# circuit_protection.net
KiCad netlist of a schematic drawn in EAGLE
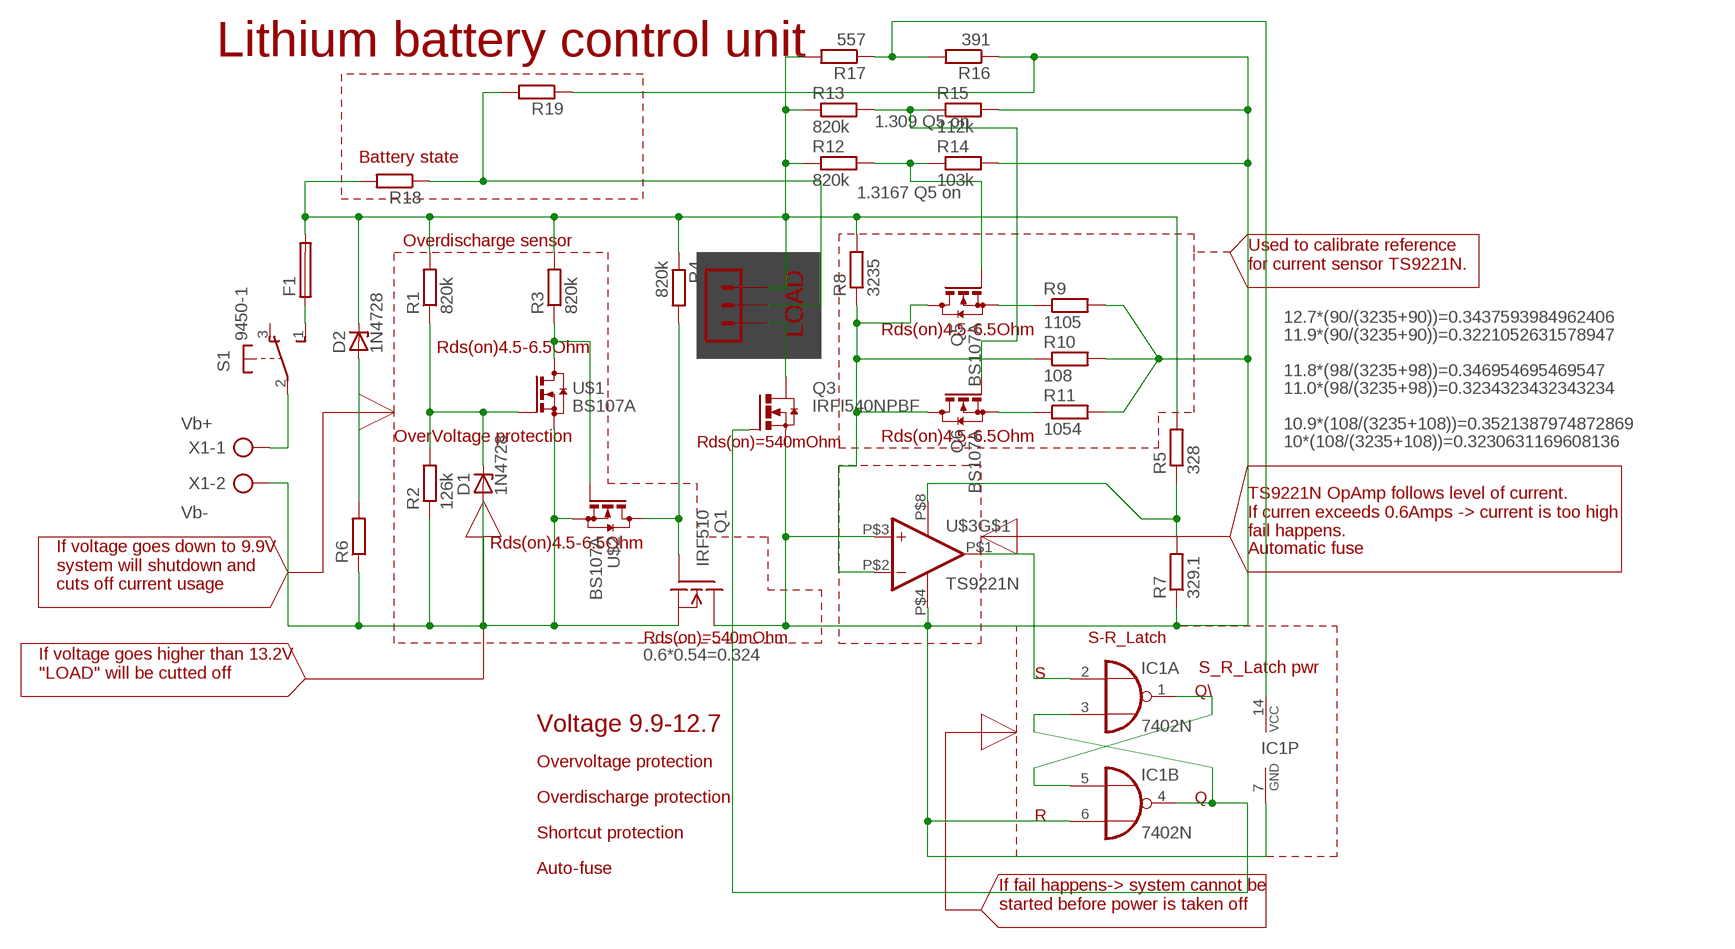
[diagram p0: schematic, sheet 1]

(export (version "E")
  (design (tool "Eeschema 10.0.6"))
  (components
    (comp (ref "D1")
      (value "1N4728")
      (footprint "eagle-import:DO41Z10")
      (libsource (lib "eagle-import") (part "1N4728"))
    )
    (comp (ref "D2")
      (value "1N4728")
      (footprint "eagle-import:DO41Z10")
      (libsource (lib "eagle-import") (part "1N4728"))
    )
    (comp (ref "F1")
      (value "GSH15")
      (footprint "eagle-import:GSH15")
      (fields (field (name "MPN") "64900001039"))
      (libsource (lib "eagle-import") (part "GSH15"))
    )
    (comp (ref "IC1")
      (value "7402N")
      (footprint "eagle-import:DIL14")
      (libsource (lib "eagle-import") (part "7402N"))
    )
    (comp (ref "Q1")
      (value "IRF510")
      (footprint "eagle-import:TO220")
      (libsource (lib "eagle-import") (part "IRF510"))
    )
    (comp (ref "Q3")
      (value "IRFI540NPBF")
      (footprint "eagle-import:TO220BH")
      (libsource (lib "eagle-import") (part "IRFI540NPBF"))
    )
    (comp (ref "Q5")
      (value "BS107A")
      (footprint "eagle-import:BC877")
      (libsource (lib "eagle-import") (part "BS107A"))
    )
    (comp (ref "Q6")
      (value "BS107A")
      (footprint "eagle-import:BC877")
      (libsource (lib "eagle-import") (part "BS107A"))
    )
    (comp (ref "R1")
      (value "820k")
      (footprint "eagle-import:0204_7")
      (libsource (lib "eagle-import") (part "R-EU_0204/7"))
    )
    (comp (ref "R2")
      (value "126k")
      (footprint "eagle-import:0204_7")
      (libsource (lib "eagle-import") (part "R-EU_0204/7"))
    )
    (comp (ref "R3")
      (value "820k")
      (footprint "eagle-import:0204_7")
      (libsource (lib "eagle-import") (part "resistor_R-EU_0204/7"))
    )
    (comp (ref "R4")
      (value "820k")
      (footprint "eagle-import:0204_7")
      (libsource (lib "eagle-import") (part "resistor_R-EU_0204/7"))
    )
    (comp (ref "R5")
      (value "328")
      (footprint "eagle-import:0204_7")
      (libsource (lib "eagle-import") (part "R-EU_0204/7"))
    )
    (comp (ref "R6")
      (value "R-EU_0204/7")
      (footprint "eagle-import:0204_7")
      (libsource (lib "eagle-import") (part "resistor_R-EU_0204/7"))
    )
    (comp (ref "R7")
      (value "329.1")
      (footprint "eagle-import:0204_7")
      (libsource (lib "eagle-import") (part "R-EU_0204/7"))
    )
    (comp (ref "R8")
      (value "3235")
      (footprint "eagle-import:0204_7")
      (libsource (lib "eagle-import") (part "R-EU_0204/7"))
    )
    (comp (ref "R9")
      (value "1105")
      (footprint "eagle-import:0204_7")
      (libsource (lib "eagle-import") (part "R-EU_0204/7"))
    )
    (comp (ref "R10")
      (value "108")
      (footprint "eagle-import:0204_7")
      (libsource (lib "eagle-import") (part "R-EU_0204/7"))
    )
    (comp (ref "R11")
      (value "1054")
      (footprint "eagle-import:0204_7")
      (libsource (lib "eagle-import") (part "R-EU_0204/7"))
    )
    (comp (ref "R12")
      (value "820k")
      (footprint "eagle-import:0204_7")
      (libsource (lib "eagle-import") (part "R-EU_0204/7"))
    )
    (comp (ref "R13")
      (value "820k")
      (footprint "eagle-import:0204_7")
      (libsource (lib "eagle-import") (part "R-EU_0204/7"))
    )
    (comp (ref "R14")
      (value "103k")
      (footprint "eagle-import:0204_7")
      (libsource (lib "eagle-import") (part "R-EU_0204/7"))
    )
    (comp (ref "R15")
      (value "112k")
      (footprint "eagle-import:0204_7")
      (libsource (lib "eagle-import") (part "R-EU_0204/7"))
    )
    (comp (ref "R16")
      (value "391")
      (footprint "eagle-import:0204_7")
      (libsource (lib "eagle-import") (part "resistor_R-EU_0204/7"))
    )
    (comp (ref "R17")
      (value "557")
      (footprint "eagle-import:0204_7")
      (libsource (lib "eagle-import") (part "resistor_R-EU_0204/7"))
    )
    (comp (ref "R18")
      (value "R-EU_0204/7")
      (footprint "eagle-import:0204_7")
      (libsource (lib "eagle-import") (part "resistor_R-EU_0204/7"))
    )
    (comp (ref "R19")
      (value "R-EU_0204/7")
      (footprint "eagle-import:0204_7")
      (libsource (lib "eagle-import") (part "resistor_R-EU_0204/7"))
    )
    (comp (ref "S1")
      (value "9450-1")
      (footprint "eagle-import:9450-1")
      (libsource (lib "eagle-import") (part "9450-1"))
    )
    (comp (ref "SV1")
      (value "MA03-1")
      (footprint "eagle-import:MA03-1")
      (libsource (lib "eagle-import") (part "MA03-1"))
    )
    (comp (ref "U$1")
      (value "BS107A")
      (footprint "eagle-import:BC877")
      (libsource (lib "eagle-import") (part "BS107A"))
    )
    (comp (ref "U$2")
      (value "BS107A")
      (footprint "eagle-import:BC877")
      (libsource (lib "eagle-import") (part "BS107A"))
    )
    (comp (ref "U$3")
      (value "TS9221N")
      (footprint "eagle-import:DIP08")
      (libsource (lib "eagle-import") (part "TS9221N"))
    )
    (comp (ref "X1")
      (value "AK300/2")
      (footprint "eagle-import:AK300_2")
      (libsource (lib "eagle-import") (part "AK300/2"))
    )
  )
  (nets
    (net (code "1") (name "Net-(D2-PadA)") (class "Default")
      (node (ref "D2") (pin "A") (pinfunction "A_A") (pintype "passive"))
      (node (ref "R6") (pin "2") (pinfunction "2_2") (pintype "passive"))
    )
    (net (code "2") (name "Net-(D2-PadC)") (class "Default")
      (node (ref "D2") (pin "C") (pinfunction "C_C") (pintype "passive"))
      (node (ref "F1") (pin "2") (pinfunction "2_2") (pintype "passive"))
      (node (ref "R1") (pin "2") (pinfunction "2_2") (pintype "passive"))
      (node (ref "R12") (pin "1") (pinfunction "1_1") (pintype "passive"))
      (node (ref "R13") (pin "1") (pinfunction "1_1") (pintype "passive"))
      (node (ref "R17") (pin "2") (pinfunction "2_2") (pintype "passive"))
      (node (ref "R18") (pin "2") (pinfunction "2_2") (pintype "passive"))
      (node (ref "R3") (pin "2") (pinfunction "2_2") (pintype "passive"))
      (node (ref "R4") (pin "1") (pinfunction "1_1") (pintype "passive"))
      (node (ref "R5") (pin "2") (pinfunction "2_2") (pintype "passive"))
      (node (ref "R8") (pin "2") (pinfunction "2_2") (pintype "passive"))
      (node (ref "SV1") (pin "3") (pinfunction "3_3") (pintype "passive"))
    )
    (net (code "3") (name "Net-(IC1A-I0)") (class "Default")
      (node (ref "IC1") (pin "2") (pinfunction "I0_2") (pintype "input"))
      (node (ref "U$3") (pin "P$1") (pinfunction "OUT_P$1") (pintype "output"))
    )
    (net (code "4") (name "Net-(IC1A-I1)") (class "Default")
      (node (ref "IC1") (pin "3") (pinfunction "I1_3") (pintype "input"))
      (node (ref "IC1") (pin "4") (pinfunction "O_4") (pintype "output"))
      (node (ref "Q3") (pin "G") (pinfunction "G_G") (pintype "passive"))
    )
    (net (code "5") (name "Net-(IC1A-O)") (class "Default")
      (node (ref "IC1") (pin "1") (pinfunction "O_1") (pintype "output"))
      (node (ref "IC1") (pin "5") (pinfunction "I0_5") (pintype "input"))
    )
    (net (code "6") (name "Net-(IC1B-I1)") (class "Default")
      (node (ref "IC1") (pin "6") (pinfunction "I1_6") (pintype "input"))
      (node (ref "IC1") (pin "7") (pinfunction "GND_7") (pintype "power_in"))
      (node (ref "Q1") (pin "2") (pinfunction "D_2") (pintype "passive"))
      (node (ref "Q3") (pin "S") (pinfunction "S_S") (pintype "passive"))
      (node (ref "R10") (pin "2") (pinfunction "2_2") (pintype "passive"))
      (node (ref "R11") (pin "2") (pinfunction "2_2") (pintype "passive"))
      (node (ref "R14") (pin "2") (pinfunction "2_2") (pintype "passive"))
      (node (ref "R15") (pin "2") (pinfunction "2_2") (pintype "passive"))
      (node (ref "R16") (pin "1") (pinfunction "1_1") (pintype "passive"))
      (node (ref "R19") (pin "1") (pinfunction "1_1") (pintype "passive"))
      (node (ref "R7") (pin "1") (pinfunction "1_1") (pintype "passive"))
      (node (ref "R9") (pin "2") (pinfunction "2_2") (pintype "passive"))
      (node (ref "U$3") (pin "P$3") (pinfunction "+IN_P$3") (pintype "input"))
      (node (ref "U$3") (pin "P$4") (pinfunction "V-_P$4") (pintype "power_in"))
    )
    (net (code "7") (name "Net-(IC1E-VCC)") (class "Default")
      (node (ref "IC1") (pin "14") (pinfunction "VCC_14") (pintype "power_in"))
      (node (ref "R16") (pin "2") (pinfunction "2_2") (pintype "passive"))
      (node (ref "R17") (pin "1") (pinfunction "1_1") (pintype "passive"))
    )
    (net (code "8") (name "Net-(Q1-G)") (class "Default")
      (node (ref "Q1") (pin "1") (pinfunction "G_1") (pintype "passive"))
      (node (ref "R4") (pin "2") (pinfunction "2_2") (pintype "passive"))
      (node (ref "U$2") (pin "1") (pinfunction "D_1") (pintype "passive"))
    )
    (net (code "9") (name "Net-(Q1-S)") (class "Default")
      (node (ref "D1") (pin "A") (pinfunction "A_A") (pintype "passive"))
      (node (ref "Q1") (pin "3") (pinfunction "S_3") (pintype "passive"))
      (node (ref "R2") (pin "1") (pinfunction "1_1") (pintype "passive"))
      (node (ref "R6") (pin "1") (pinfunction "1_1") (pintype "passive"))
      (node (ref "U$1") (pin "3") (pinfunction "S_3") (pintype "passive"))
      (node (ref "U$2") (pin "3") (pinfunction "S_3") (pintype "passive"))
      (node (ref "X1") (pin "2") (pinfunction "KL_2") (pintype "passive"))
    )
    (net (code "10") (name "Net-(Q3-PadD)") (class "Default")
      (node (ref "Q3") (pin "D") (pinfunction "D_D") (pintype "passive"))
      (node (ref "SV1") (pin "1") (pinfunction "1_1") (pintype "passive"))
    )
    (net (code "11") (name "Net-(Q5-D)") (class "Default")
      (node (ref "Q5") (pin "1") (pinfunction "D_1") (pintype "passive"))
      (node (ref "Q6") (pin "1") (pinfunction "D_1") (pintype "passive"))
      (node (ref "R10") (pin "1") (pinfunction "1_1") (pintype "passive"))
      (node (ref "R8") (pin "1") (pinfunction "1_1") (pintype "passive"))
      (node (ref "U$3") (pin "P$2") (pinfunction "-IN_P$2") (pintype "input"))
    )
    (net (code "12") (name "Net-(Q5-G)") (class "Default")
      (node (ref "Q5") (pin "2") (pinfunction "G_2") (pintype "passive"))
      (node (ref "R12") (pin "2") (pinfunction "2_2") (pintype "passive"))
      (node (ref "R14") (pin "1") (pinfunction "1_1") (pintype "passive"))
    )
    (net (code "13") (name "Net-(Q5-S)") (class "Default")
      (node (ref "Q5") (pin "3") (pinfunction "S_3") (pintype "passive"))
      (node (ref "R9") (pin "1") (pinfunction "1_1") (pintype "passive"))
    )
    (net (code "14") (name "Net-(Q6-G)") (class "Default")
      (node (ref "Q6") (pin "2") (pinfunction "G_2") (pintype "passive"))
      (node (ref "R13") (pin "2") (pinfunction "2_2") (pintype "passive"))
      (node (ref "R15") (pin "1") (pinfunction "1_1") (pintype "passive"))
    )
    (net (code "15") (name "Net-(Q6-S)") (class "Default")
      (node (ref "Q6") (pin "3") (pinfunction "S_3") (pintype "passive"))
      (node (ref "R11") (pin "1") (pinfunction "1_1") (pintype "passive"))
    )
    (net (code "16") (name "Net-(R18-Pad1)") (class "Default")
      (node (ref "R18") (pin "1") (pinfunction "1_1") (pintype "passive"))
      (node (ref "R19") (pin "2") (pinfunction "2_2") (pintype "passive"))
      (node (ref "SV1") (pin "2") (pinfunction "2_2") (pintype "passive"))
    )
    (net (code "17") (name "Net-(S1-P)") (class "Default")
      (node (ref "S1") (pin "2") (pinfunction "P_2") (pintype "passive"))
      (node (ref "X1") (pin "1") (pinfunction "KL_1") (pintype "passive"))
    )
    (net (code "18") (name "Net-(S1-S)") (class "Default")
      (node (ref "F1") (pin "1") (pinfunction "1_1") (pintype "passive"))
      (node (ref "S1") (pin "1") (pinfunction "S_1") (pintype "passive"))
    )
    (net (code "19") (name "Net-(U$1-D)") (class "Default")
      (node (ref "R3") (pin "1") (pinfunction "1_1") (pintype "passive"))
      (node (ref "U$1") (pin "1") (pinfunction "D_1") (pintype "passive"))
      (node (ref "U$2") (pin "2") (pinfunction "G_2") (pintype "passive"))
    )
    (net (code "20") (name "Net-(U$1-G)") (class "Default")
      (node (ref "D1") (pin "C") (pinfunction "C_C") (pintype "passive"))
      (node (ref "R1") (pin "1") (pinfunction "1_1") (pintype "passive"))
      (node (ref "R2") (pin "2") (pinfunction "2_2") (pintype "passive"))
      (node (ref "U$1") (pin "2") (pinfunction "G_2") (pintype "passive"))
    )
    (net (code "21") (name "Net-(U$3A-V+)") (class "Default")
      (node (ref "R5") (pin "1") (pinfunction "1_1") (pintype "passive"))
      (node (ref "R7") (pin "2") (pinfunction "2_2") (pintype "passive"))
      (node (ref "U$3") (pin "P$8") (pinfunction "V+_P$8") (pintype "power_in"))
    )
    (net (code "22") (name "unconnected-(S1-O-Pad3)") (class "Default")
      (node (ref "S1") (pin "3") (pinfunction "O_3") (pintype "passive"))
    )
  )
)
